# battery_buzzer_jig.net
KiCad netlist of a schematic drawn in EAGLE
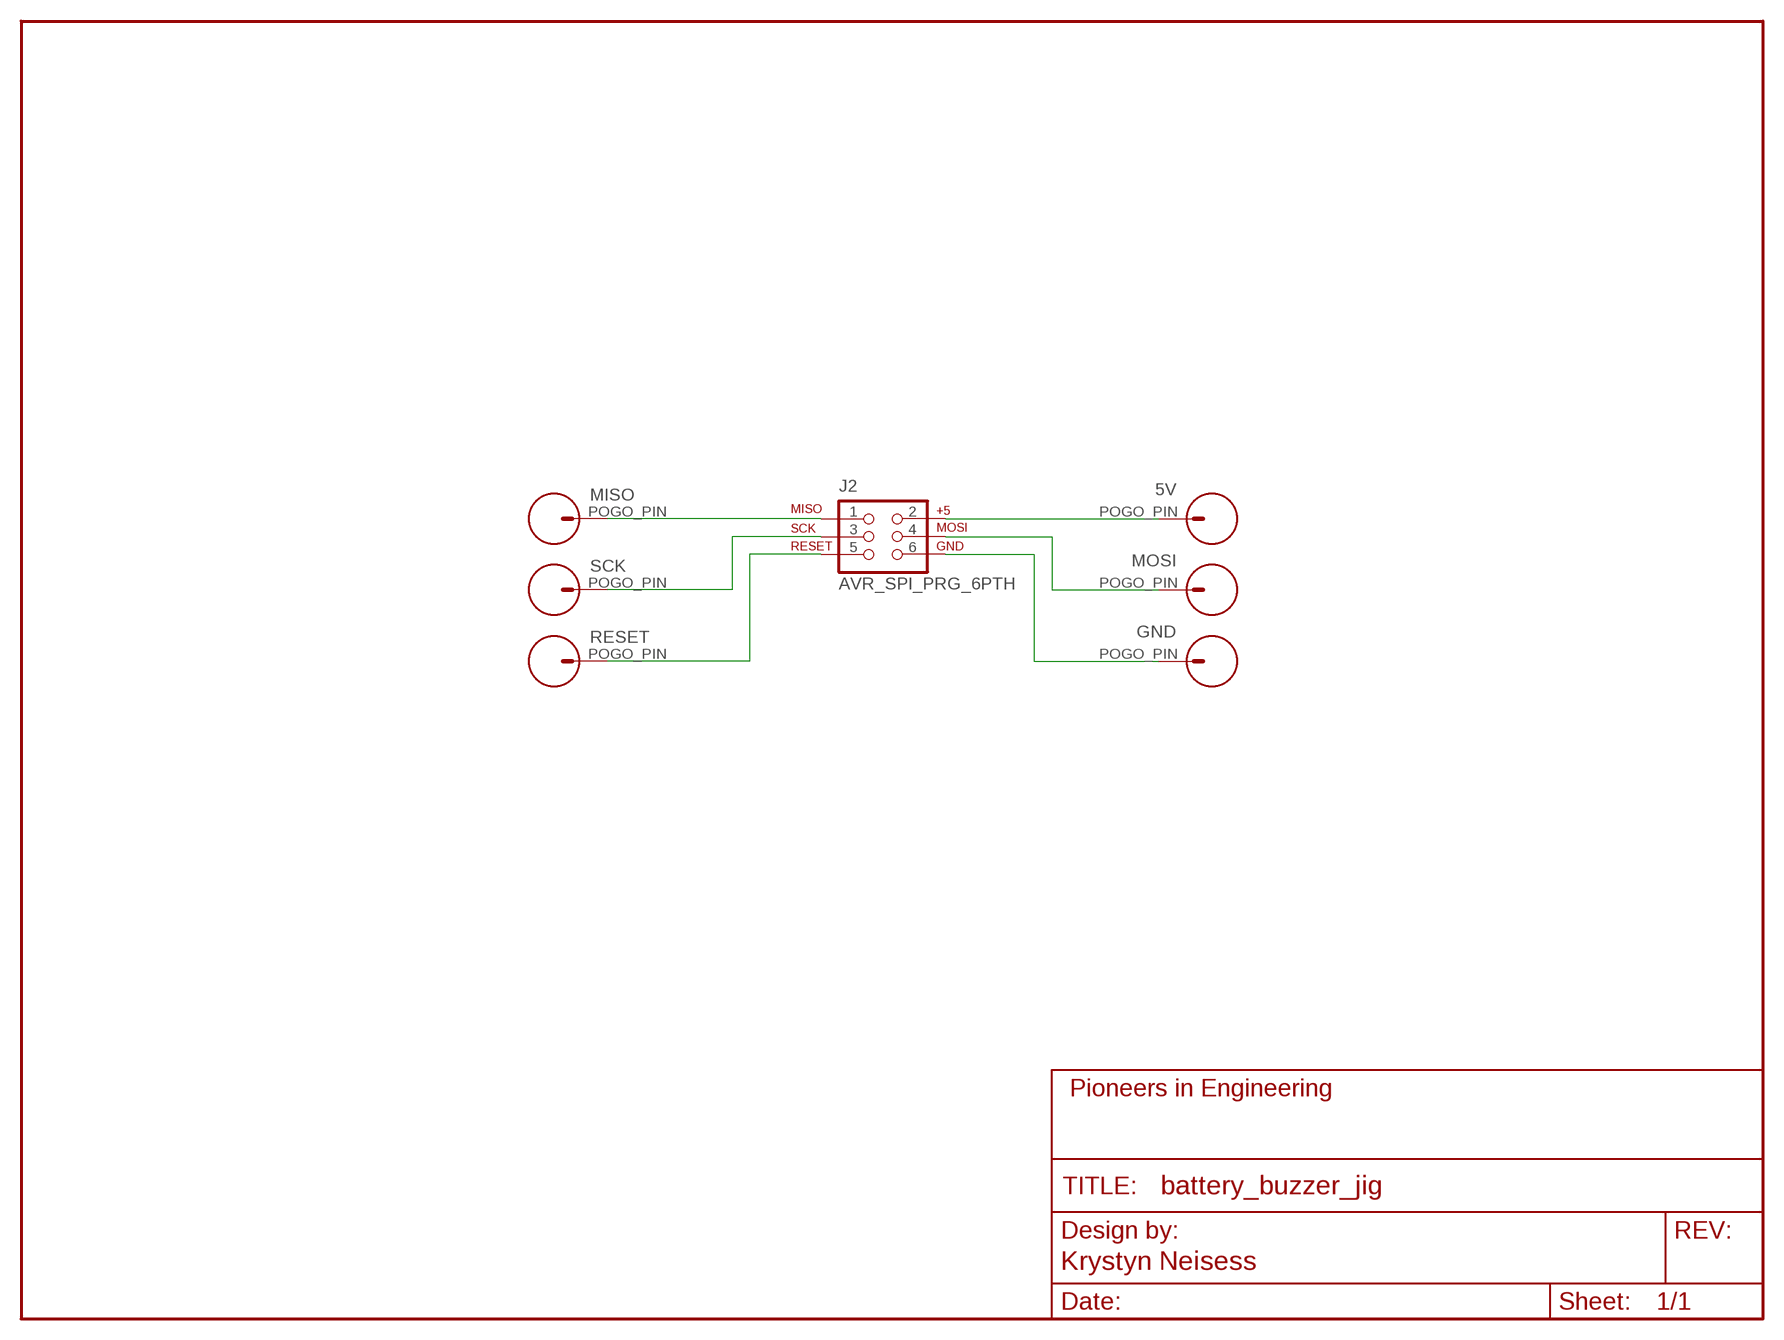
[diagram p0: schematic, sheet 1]

(export (version "E")
  (design (tool "Eeschema 10.0.6"))
  (components
    (comp (ref "5V")
      (value "POGO_PIN")
      (footprint "eagle-import:POGO_PIN_394")
      (libsource (lib "eagle-import") (part "POGO_PIN"))
    )
    (comp (ref "GND")
      (value "POGO_PIN")
      (footprint "eagle-import:POGO_PIN_394")
      (libsource (lib "eagle-import") (part "POGO_PIN"))
    )
    (comp (ref "J2")
      (value "AVR_SPI_PRG_6PTH")
      (footprint "eagle-import:2X3")
      (libsource (lib "eagle-import") (part "AVR_SPI_PRG_6PTH"))
    )
    (comp (ref "MISO")
      (value "POGO_PIN")
      (footprint "eagle-import:POGO_PIN_394")
      (libsource (lib "eagle-import") (part "POGO_PIN"))
    )
    (comp (ref "MOSI")
      (value "POGO_PIN")
      (footprint "eagle-import:POGO_PIN_394")
      (libsource (lib "eagle-import") (part "POGO_PIN"))
    )
    (comp (ref "RESET")
      (value "POGO_PIN")
      (footprint "eagle-import:POGO_PIN_394")
      (libsource (lib "eagle-import") (part "POGO_PIN"))
    )
    (comp (ref "SCK")
      (value "POGO_PIN")
      (footprint "eagle-import:POGO_PIN_394")
      (libsource (lib "eagle-import") (part "POGO_PIN"))
    )
  )
  (nets
    (net (code "1") (name "Net-(5V-P$1)") (class "Default")
      (node (ref "5V") (pin "POGO_PIN") (pinfunction "P$1_POGO_PIN") (pintype "bidirectional"))
      (node (ref "J2") (pin "2") (pinfunction "2_2") (pintype "passive"))
    )
    (net (code "2") (name "Net-(GND-P$1)") (class "Default")
      (node (ref "GND") (pin "POGO_PIN") (pinfunction "P$1_POGO_PIN") (pintype "bidirectional"))
      (node (ref "J2") (pin "6") (pinfunction "6_6") (pintype "passive"))
    )
    (net (code "3") (name "Net-(MISO-P$1)") (class "Default")
      (node (ref "J2") (pin "1") (pinfunction "1_1") (pintype "passive"))
      (node (ref "MISO") (pin "POGO_PIN") (pinfunction "P$1_POGO_PIN") (pintype "bidirectional"))
    )
    (net (code "4") (name "Net-(MOSI-P$1)") (class "Default")
      (node (ref "J2") (pin "4") (pinfunction "4_4") (pintype "passive"))
      (node (ref "MOSI") (pin "POGO_PIN") (pinfunction "P$1_POGO_PIN") (pintype "bidirectional"))
    )
    (net (code "5") (name "Net-(RESET-P$1)") (class "Default")
      (node (ref "J2") (pin "5") (pinfunction "5_5") (pintype "passive"))
      (node (ref "RESET") (pin "POGO_PIN") (pinfunction "P$1_POGO_PIN") (pintype "bidirectional"))
    )
    (net (code "6") (name "Net-(SCK-P$1)") (class "Default")
      (node (ref "J2") (pin "3") (pinfunction "3_3") (pintype "passive"))
      (node (ref "SCK") (pin "POGO_PIN") (pinfunction "P$1_POGO_PIN") (pintype "bidirectional"))
    )
  )
)
